# PSD_PMIC.net
KiCad netlist of a schematic drawn in Altium Designer
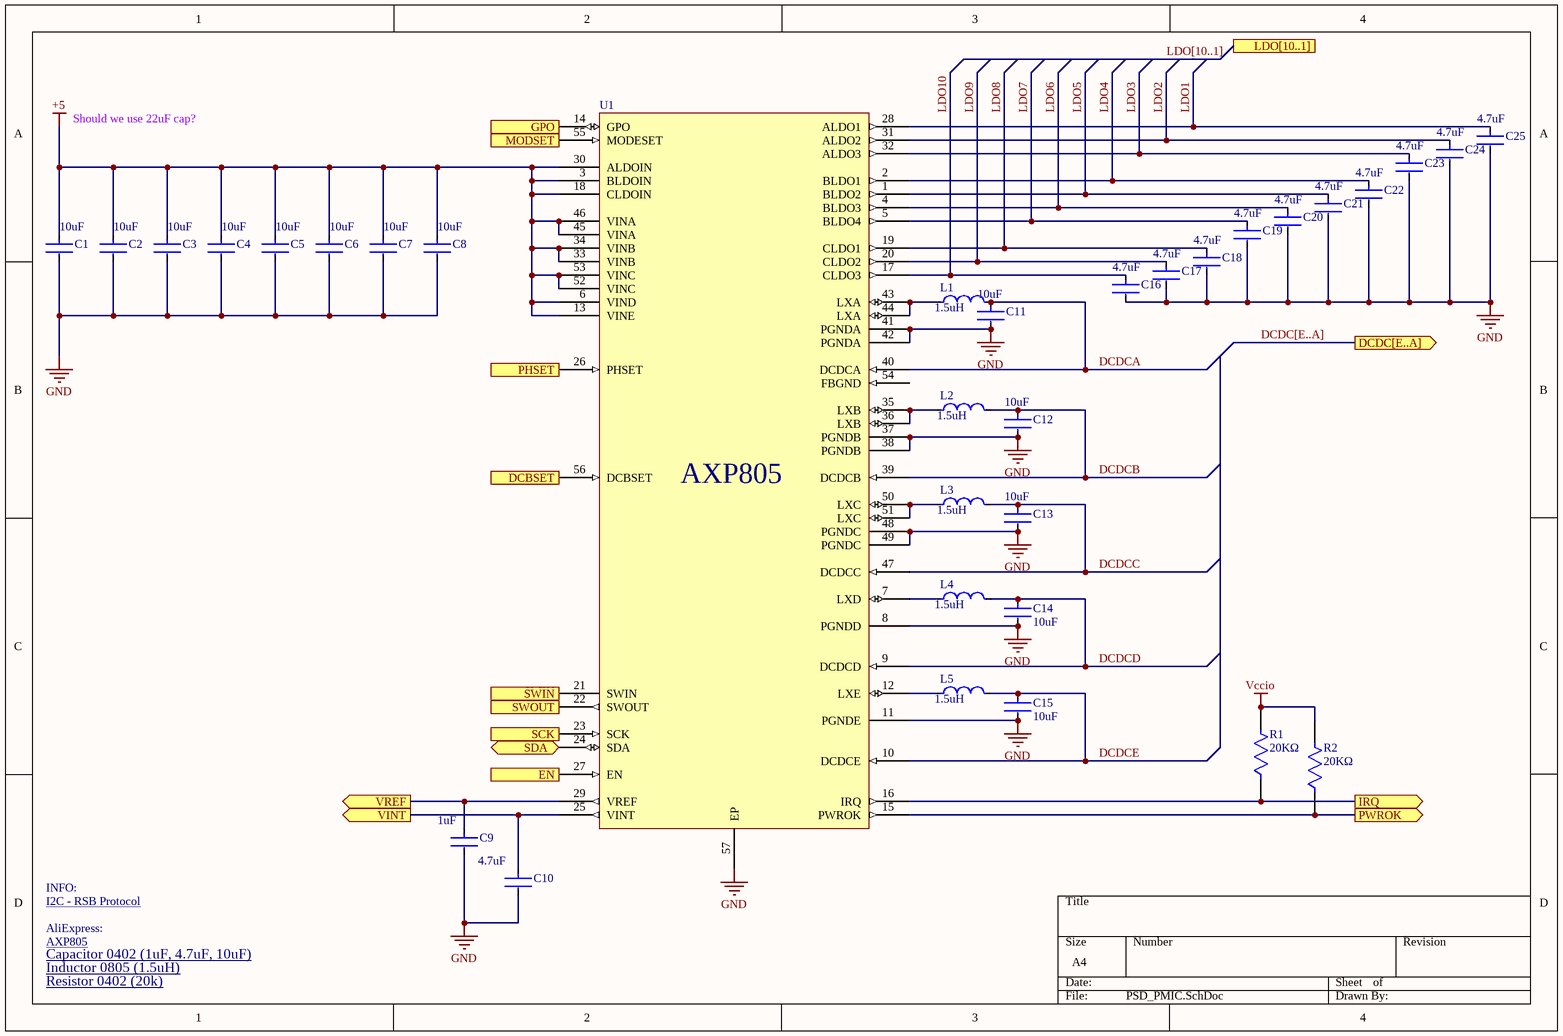
[diagram p0: PSD_PMIC.SchDoc]

(export (version "E")
  (design (tool "Eeschema 10.0.6"))
  (components
    (comp (ref "C1")
      (value "CL05A106MP5NUNC")
      (footprint "FP-CL05A106MP5NUNC-MFG")
      (description "CAP CER 10UF 10V X5R 0402")
      (fields
        (field (name "OCTOPART") "https://octopart.com/cl05a106mp5nunc-samsung-22457395")
        (field (name "TOLERANCE") "20%")
        (field (name "CAPACITANCE") "10uF")
      )
      (libsource (lib "Altium Content Vault") (part "b4654b650e69147ec39a6b967a45e02"))
    )
    (comp (ref "C2")
      (value "CL05A106MP5NUNC")
      (footprint "FP-CL05A106MP5NUNC-MFG")
      (description "CAP CER 10UF 10V X5R 0402")
      (fields
        (field (name "OCTOPART") "https://octopart.com/cl05a106mp5nunc-samsung-22457395")
        (field (name "TOLERANCE") "20%")
        (field (name "CAPACITANCE") "10uF")
      )
      (libsource (lib "Altium Content Vault") (part "b4654b650e69147ec39a6b967a45e02"))
    )
    (comp (ref "C3")
      (value "CL05A106MP5NUNC")
      (footprint "FP-CL05A106MP5NUNC-MFG")
      (description "CAP CER 10UF 10V X5R 0402")
      (fields
        (field (name "OCTOPART") "https://octopart.com/cl05a106mp5nunc-samsung-22457395")
        (field (name "TOLERANCE") "20%")
        (field (name "CAPACITANCE") "10uF")
      )
      (libsource (lib "Altium Content Vault") (part "b4654b650e69147ec39a6b967a45e02"))
    )
    (comp (ref "C4")
      (value "CL05A106MP5NUNC")
      (footprint "FP-CL05A106MP5NUNC-MFG")
      (description "CAP CER 10UF 10V X5R 0402")
      (fields
        (field (name "OCTOPART") "https://octopart.com/cl05a106mp5nunc-samsung-22457395")
        (field (name "TOLERANCE") "20%")
        (field (name "CAPACITANCE") "10uF")
      )
      (libsource (lib "Altium Content Vault") (part "b4654b650e69147ec39a6b967a45e02"))
    )
    (comp (ref "C5")
      (value "CL05A106MP5NUNC")
      (footprint "FP-CL05A106MP5NUNC-MFG")
      (description "CAP CER 10UF 10V X5R 0402")
      (fields
        (field (name "OCTOPART") "https://octopart.com/cl05a106mp5nunc-samsung-22457395")
        (field (name "TOLERANCE") "20%")
        (field (name "CAPACITANCE") "10uF")
      )
      (libsource (lib "Altium Content Vault") (part "b4654b650e69147ec39a6b967a45e02"))
    )
    (comp (ref "C6")
      (value "CL05A106MP5NUNC")
      (footprint "FP-CL05A106MP5NUNC-MFG")
      (description "CAP CER 10UF 10V X5R 0402")
      (fields
        (field (name "OCTOPART") "https://octopart.com/cl05a106mp5nunc-samsung-22457395")
        (field (name "TOLERANCE") "20%")
        (field (name "CAPACITANCE") "10uF")
      )
      (libsource (lib "Altium Content Vault") (part "b4654b650e69147ec39a6b967a45e02"))
    )
    (comp (ref "C7")
      (value "CL05A106MP5NUNC")
      (footprint "FP-CL05A106MP5NUNC-MFG")
      (description "CAP CER 10UF 10V X5R 0402")
      (fields
        (field (name "OCTOPART") "https://octopart.com/cl05a106mp5nunc-samsung-22457395")
        (field (name "TOLERANCE") "20%")
        (field (name "CAPACITANCE") "10uF")
      )
      (libsource (lib "Altium Content Vault") (part "b4654b650e69147ec39a6b967a45e02"))
    )
    (comp (ref "C8")
      (value "CL05A106MP5NUNC")
      (footprint "FP-CL05A106MP5NUNC-MFG")
      (description "CAP CER 10UF 10V X5R 0402")
      (fields
        (field (name "OCTOPART") "https://octopart.com/cl05a106mp5nunc-samsung-22457395")
        (field (name "TOLERANCE") "20%")
        (field (name "CAPACITANCE") "10uF")
      )
      (libsource (lib "Altium Content Vault") (part "b4654b650e69147ec39a6b967a45e02"))
    )
    (comp (ref "C9")
      (value "CL05B105KQ5NQNC")
      (footprint "FP-CL95-IPC_C")
      (description "Cap Ceramic 1uF 6.3V X7R ±10% SMD 0402 +125°C Paper T/R")
      (fields (field (name "CAPACITANCE") "1uF") (field (name "TOLERANCE") "10%"))
      (libsource (lib "Altium Content Vault") (part "b4654b650e69147ec39a6b967a45e02"))
    )
    (comp (ref "C10")
      (value "CL05A475KP5NRNC")
      (footprint "FP-CL828-IPC_C")
      (description "Cap Ceramic 4.7uF 10V X5R ±10% SMD 0402 +85°C Paper T/R")
      (fields (field (name "CAPACITANCE") "4.7uF") (field (name "TOLERANCE") "10%"))
      (libsource (lib "Altium Content Vault") (part "b4654b650e69147ec39a6b967a45e02"))
    )
    (comp (ref "C11")
      (value "CL05A106MP5NUNC")
      (footprint "FP-CL05A106MP5NUNC-MFG")
      (description "CAP CER 10UF 10V X5R 0402")
      (fields
        (field (name "OCTOPART") "https://octopart.com/cl05a106mp5nunc-samsung-22457395")
        (field (name "TOLERANCE") "20%")
        (field (name "CAPACITANCE") "10uF")
      )
      (libsource (lib "Altium Content Vault") (part "b4654b650e69147ec39a6b967a45e02"))
    )
    (comp (ref "C12")
      (value "CL05A106MP5NUNC")
      (footprint "FP-CL05A106MP5NUNC-MFG")
      (description "CAP CER 10UF 10V X5R 0402")
      (fields
        (field (name "OCTOPART") "https://octopart.com/cl05a106mp5nunc-samsung-22457395")
        (field (name "TOLERANCE") "20%")
        (field (name "CAPACITANCE") "10uF")
      )
      (libsource (lib "Altium Content Vault") (part "b4654b650e69147ec39a6b967a45e02"))
    )
    (comp (ref "C13")
      (value "CL05A106MP5NUNC")
      (footprint "FP-CL05A106MP5NUNC-MFG")
      (description "CAP CER 10UF 10V X5R 0402")
      (fields
        (field (name "OCTOPART") "https://octopart.com/cl05a106mp5nunc-samsung-22457395")
        (field (name "TOLERANCE") "20%")
        (field (name "CAPACITANCE") "10uF")
      )
      (libsource (lib "Altium Content Vault") (part "b4654b650e69147ec39a6b967a45e02"))
    )
    (comp (ref "C14")
      (value "CL05A106MP5NUNC")
      (footprint "FP-CL05A106MP5NUNC-MFG")
      (description "CAP CER 10UF 10V X5R 0402")
      (fields
        (field (name "OCTOPART") "https://octopart.com/cl05a106mp5nunc-samsung-22457395")
        (field (name "TOLERANCE") "20%")
        (field (name "CAPACITANCE") "10uF")
      )
      (libsource (lib "Altium Content Vault") (part "b4654b650e69147ec39a6b967a45e02"))
    )
    (comp (ref "C15")
      (value "CL05A106MP5NUNC")
      (footprint "FP-CL05A106MP5NUNC-MFG")
      (description "CAP CER 10UF 10V X5R 0402")
      (fields
        (field (name "OCTOPART") "https://octopart.com/cl05a106mp5nunc-samsung-22457395")
        (field (name "TOLERANCE") "20%")
        (field (name "CAPACITANCE") "10uF")
      )
      (libsource (lib "Altium Content Vault") (part "b4654b650e69147ec39a6b967a45e02"))
    )
    (comp (ref "C16")
      (value "CL05A475KP5NRNC")
      (footprint "FP-CL828-IPC_C")
      (description "Cap Ceramic 4.7uF 10V X5R ±10% SMD 0402 +85°C Paper T/R")
      (fields (field (name "CAPACITANCE") "4.7uF") (field (name "TOLERANCE") "10%"))
      (libsource (lib "Altium Content Vault") (part "b4654b650e69147ec39a6b967a45e02"))
    )
    (comp (ref "C17")
      (value "CL05A475KP5NRNC")
      (footprint "FP-CL828-IPC_C")
      (description "Cap Ceramic 4.7uF 10V X5R ±10% SMD 0402 +85°C Paper T/R")
      (fields (field (name "CAPACITANCE") "4.7uF") (field (name "TOLERANCE") "10%"))
      (libsource (lib "Altium Content Vault") (part "b4654b650e69147ec39a6b967a45e02"))
    )
    (comp (ref "C18")
      (value "CL05A475KP5NRNC")
      (footprint "FP-CL828-IPC_C")
      (description "Cap Ceramic 4.7uF 10V X5R ±10% SMD 0402 +85°C Paper T/R")
      (fields (field (name "CAPACITANCE") "4.7uF") (field (name "TOLERANCE") "10%"))
      (libsource (lib "Altium Content Vault") (part "b4654b650e69147ec39a6b967a45e02"))
    )
    (comp (ref "C19")
      (value "CL05A475KP5NRNC")
      (footprint "FP-CL828-IPC_C")
      (description "Cap Ceramic 4.7uF 10V X5R ±10% SMD 0402 +85°C Paper T/R")
      (fields (field (name "CAPACITANCE") "4.7uF") (field (name "TOLERANCE") "10%"))
      (libsource (lib "Altium Content Vault") (part "b4654b650e69147ec39a6b967a45e02"))
    )
    (comp (ref "C20")
      (value "CL05A475KP5NRNC")
      (footprint "FP-CL828-IPC_C")
      (description "Cap Ceramic 4.7uF 10V X5R ±10% SMD 0402 +85°C Paper T/R")
      (fields (field (name "CAPACITANCE") "4.7uF") (field (name "TOLERANCE") "10%"))
      (libsource (lib "Altium Content Vault") (part "b4654b650e69147ec39a6b967a45e02"))
    )
    (comp (ref "C21")
      (value "CL05A475KP5NRNC")
      (footprint "FP-CL828-IPC_C")
      (description "Cap Ceramic 4.7uF 10V X5R ±10% SMD 0402 +85°C Paper T/R")
      (fields (field (name "CAPACITANCE") "4.7uF") (field (name "TOLERANCE") "10%"))
      (libsource (lib "Altium Content Vault") (part "b4654b650e69147ec39a6b967a45e02"))
    )
    (comp (ref "C22")
      (value "CL05A475KP5NRNC")
      (footprint "FP-CL828-IPC_C")
      (description "Cap Ceramic 4.7uF 10V X5R ±10% SMD 0402 +85°C Paper T/R")
      (fields (field (name "CAPACITANCE") "4.7uF") (field (name "TOLERANCE") "10%"))
      (libsource (lib "Altium Content Vault") (part "b4654b650e69147ec39a6b967a45e02"))
    )
    (comp (ref "C23")
      (value "CL05A475KP5NRNC")
      (footprint "FP-CL828-IPC_C")
      (description "Cap Ceramic 4.7uF 10V X5R ±10% SMD 0402 +85°C Paper T/R")
      (fields (field (name "CAPACITANCE") "4.7uF") (field (name "TOLERANCE") "10%"))
      (libsource (lib "Altium Content Vault") (part "b4654b650e69147ec39a6b967a45e02"))
    )
    (comp (ref "C24")
      (value "CL05A475KP5NRNC")
      (footprint "FP-CL828-IPC_C")
      (description "Cap Ceramic 4.7uF 10V X5R ±10% SMD 0402 +85°C Paper T/R")
      (fields (field (name "CAPACITANCE") "4.7uF") (field (name "TOLERANCE") "10%"))
      (libsource (lib "Altium Content Vault") (part "b4654b650e69147ec39a6b967a45e02"))
    )
    (comp (ref "C25")
      (value "CL05A475KP5NRNC")
      (footprint "FP-CL828-IPC_C")
      (description "Cap Ceramic 4.7uF 10V X5R ±10% SMD 0402 +85°C Paper T/R")
      (fields (field (name "CAPACITANCE") "4.7uF") (field (name "TOLERANCE") "10%"))
      (libsource (lib "Altium Content Vault") (part "b4654b650e69147ec39a6b967a45e02"))
    )
    (comp (ref "L1")
      (value "LQM21NN1R5K10D")
      (footprint "FP-LQM21DN_00-MFG")
      (description "Multilayer Type Inductor for General Circuits, 0805 (2012), 1.5μH, 10%, 0.5Ω, 50mA")
      (fields (field (name "TOLERANCE") "10%") (field (name "INDUCTANCE") "1.5uH"))
      (libsource (lib "Altium Content Vault") (part "725321dda6339637d4d059423bc1c3c"))
    )
    (comp (ref "L2")
      (value "LQM21NN1R5K10D")
      (footprint "FP-LQM21DN_00-MFG")
      (description "Multilayer Type Inductor for General Circuits, 0805 (2012), 1.5μH, 10%, 0.5Ω, 50mA")
      (fields (field (name "TOLERANCE") "10%") (field (name "INDUCTANCE") "1.5uH"))
      (libsource (lib "Altium Content Vault") (part "725321dda6339637d4d059423bc1c3c"))
    )
    (comp (ref "L3")
      (value "LQM21NN1R5K10D")
      (footprint "FP-LQM21DN_00-MFG")
      (description "Multilayer Type Inductor for General Circuits, 0805 (2012), 1.5μH, 10%, 0.5Ω, 50mA")
      (fields (field (name "TOLERANCE") "10%") (field (name "INDUCTANCE") "1.5uH"))
      (libsource (lib "Altium Content Vault") (part "725321dda6339637d4d059423bc1c3c"))
    )
    (comp (ref "L4")
      (value "LQM21NN1R5K10D")
      (footprint "FP-LQM21DN_00-MFG")
      (description "Multilayer Type Inductor for General Circuits, 0805 (2012), 1.5μH, 10%, 0.5Ω, 50mA")
      (fields (field (name "TOLERANCE") "10%") (field (name "INDUCTANCE") "1.5uH"))
      (libsource (lib "Altium Content Vault") (part "725321dda6339637d4d059423bc1c3c"))
    )
    (comp (ref "L5")
      (value "LQM21NN1R5K10D")
      (footprint "FP-LQM21DN_00-MFG")
      (description "Multilayer Type Inductor for General Circuits, 0805 (2012), 1.5μH, 10%, 0.5Ω, 50mA")
      (fields (field (name "TOLERANCE") "10%") (field (name "INDUCTANCE") "1.5uH"))
      (libsource (lib "Altium Content Vault") (part "725321dda6339637d4d059423bc1c3c"))
    )
    (comp (ref "R1")
      (value "20KΩ")
      (footprint "FP-RT0402-MFG")
      (description "RES SMD 20K OHM 0.1% 1/16W 0402")
      (fields
        (field (name "MANUFACTURER PART NUMBER") "RT0402BRD0720KL")
        (field (name "OCTOPART") "https://octopart.com/rt0402brd0720kl-yageo-1422805")
      )
      (libsource (lib "Altium Content Vault") (part "1029c3af85768c4190bb7ad29bc67b5"))
    )
    (comp (ref "R2")
      (value "20KΩ")
      (footprint "FP-RT0402-MFG")
      (description "RES SMD 20K OHM 0.1% 1/16W 0402")
      (fields
        (field (name "MANUFACTURER PART NUMBER") "RT0402BRD0720KL")
        (field (name "OCTOPART") "https://octopart.com/rt0402brd0720kl-yageo-1422805")
      )
      (libsource (lib "Altium Content Vault") (part "1029c3af85768c4190bb7ad29bc67b5"))
    )
    (comp (ref "U1")
      (value "UQFN127P600-8N")
      (footprint "UQFN127P600-8N")
      (libsource (lib "CUSTOM") (part "UQFN127P600-8N"))
    )
  )
  (nets
    (net (code "2") (name "+5") (class "Default")
      (node (ref "C1") (pin "1") (pinfunction "1_1") (pintype "passive"))
      (node (ref "C2") (pin "1") (pinfunction "1_1") (pintype "passive"))
      (node (ref "C3") (pin "1") (pinfunction "1_1") (pintype "passive"))
      (node (ref "C4") (pin "1") (pinfunction "1_1") (pintype "passive"))
      (node (ref "C5") (pin "1") (pinfunction "1_1") (pintype "passive"))
      (node (ref "C6") (pin "1") (pinfunction "1_1") (pintype "passive"))
      (node (ref "C7") (pin "1") (pinfunction "1_1") (pintype "passive"))
      (node (ref "C8") (pin "1") (pinfunction "1_1") (pintype "passive"))
      (node (ref "U1") (pin "13") (pinfunction "VINE_13") (pintype "power_in"))
      (node (ref "U1") (pin "18") (pinfunction "CLDOIN_18") (pintype "power_in"))
      (node (ref "U1") (pin "3") (pinfunction "BLDOIN_3") (pintype "power_in"))
      (node (ref "U1") (pin "30") (pinfunction "ALDOIN_30") (pintype "power_in"))
      (node (ref "U1") (pin "33") (pinfunction "VINB_33") (pintype "power_in"))
      (node (ref "U1") (pin "34") (pinfunction "VINB_34") (pintype "power_in"))
      (node (ref "U1") (pin "45") (pinfunction "VINA_45") (pintype "power_in"))
      (node (ref "U1") (pin "46") (pinfunction "VINA_46") (pintype "power_in"))
      (node (ref "U1") (pin "52") (pinfunction "VINC_52") (pintype "power_in"))
      (node (ref "U1") (pin "53") (pinfunction "VINC_53") (pintype "power_in"))
      (node (ref "U1") (pin "6") (pinfunction "VIND_6") (pintype "power_in"))
    )
    (net (code "3") (name "/DCBSET") (class "Default")
      (node (ref "U1") (pin "56") (pinfunction "DCBSET_56") (pintype "input"))
    )
    (net (code "4") (name "/DCDCA") (class "Default")
      (node (ref "C11") (pin "1") (pinfunction "1_1") (pintype "passive"))
      (node (ref "L1") (pin "2") (pinfunction "2_2") (pintype "passive"))
      (node (ref "U1") (pin "40") (pinfunction "DCDCA_40") (pintype "input"))
    )
    (net (code "5") (name "/DCDCB") (class "Default")
      (node (ref "C12") (pin "1") (pinfunction "1_1") (pintype "passive"))
      (node (ref "L2") (pin "2") (pinfunction "2_2") (pintype "passive"))
      (node (ref "U1") (pin "39") (pinfunction "DCDCB_39") (pintype "input"))
    )
    (net (code "6") (name "/DCDCC") (class "Default")
      (node (ref "C13") (pin "1") (pinfunction "1_1") (pintype "passive"))
      (node (ref "L3") (pin "2") (pinfunction "2_2") (pintype "passive"))
      (node (ref "U1") (pin "47") (pinfunction "DCDCC_47") (pintype "input"))
    )
    (net (code "7") (name "/DCDCD") (class "Default")
      (node (ref "C14") (pin "1") (pinfunction "1_1") (pintype "passive"))
      (node (ref "L4") (pin "2") (pinfunction "2_2") (pintype "passive"))
      (node (ref "U1") (pin "9") (pinfunction "DCDCD_9") (pintype "input"))
    )
    (net (code "8") (name "/DCDCE") (class "Default")
      (node (ref "C15") (pin "1") (pinfunction "1_1") (pintype "passive"))
      (node (ref "L5") (pin "2") (pinfunction "2_2") (pintype "passive"))
      (node (ref "U1") (pin "10") (pinfunction "DCDCE_10") (pintype "input"))
    )
    (net (code "9") (name "/EN") (class "Default")
      (node (ref "U1") (pin "27") (pinfunction "EN_27") (pintype "input"))
    )
    (net (code "10") (name "/GPO") (class "Default")
      (node (ref "U1") (pin "14") (pinfunction "GPO_14") (pintype "bidirectional"))
    )
    (net (code "11") (name "/IRQ") (class "Default")
      (node (ref "R1") (pin "1") (pinfunction "1_1") (pintype "passive"))
      (node (ref "U1") (pin "16") (pinfunction "IRQ_16") (pintype "output"))
    )
    (net (code "12") (name "/LDO1") (class "Default")
      (node (ref "C25") (pin "1") (pinfunction "1_1") (pintype "passive"))
      (node (ref "U1") (pin "28") (pinfunction "ALDO1_28") (pintype "output"))
    )
    (net (code "13") (name "/LDO2") (class "Default")
      (node (ref "C24") (pin "1") (pinfunction "1_1") (pintype "passive"))
      (node (ref "U1") (pin "31") (pinfunction "ALDO2_31") (pintype "output"))
    )
    (net (code "14") (name "/LDO3") (class "Default")
      (node (ref "C23") (pin "1") (pinfunction "1_1") (pintype "passive"))
      (node (ref "U1") (pin "32") (pinfunction "ALDO3_32") (pintype "output"))
    )
    (net (code "15") (name "/LDO4") (class "Default")
      (node (ref "C22") (pin "1") (pinfunction "1_1") (pintype "passive"))
      (node (ref "U1") (pin "2") (pinfunction "BLDO1_2") (pintype "output"))
    )
    (net (code "16") (name "/LDO5") (class "Default")
      (node (ref "C21") (pin "1") (pinfunction "1_1") (pintype "passive"))
      (node (ref "U1") (pin "1") (pinfunction "BLDO2_1") (pintype "output"))
    )
    (net (code "17") (name "/LDO6") (class "Default")
      (node (ref "C20") (pin "1") (pinfunction "1_1") (pintype "passive"))
      (node (ref "U1") (pin "4") (pinfunction "BLDO3_4") (pintype "output"))
    )
    (net (code "18") (name "/LDO7") (class "Default")
      (node (ref "C19") (pin "1") (pinfunction "1_1") (pintype "passive"))
      (node (ref "U1") (pin "5") (pinfunction "BLDO4_5") (pintype "output"))
    )
    (net (code "19") (name "/LDO8") (class "Default")
      (node (ref "C18") (pin "1") (pinfunction "1_1") (pintype "passive"))
      (node (ref "U1") (pin "19") (pinfunction "CLDO1_19") (pintype "output"))
    )
    (net (code "20") (name "/LDO9") (class "Default")
      (node (ref "C17") (pin "1") (pinfunction "1_1") (pintype "passive"))
      (node (ref "U1") (pin "20") (pinfunction "CLDO2_20") (pintype "output"))
    )
    (net (code "21") (name "/LDO10") (class "Default")
      (node (ref "C16") (pin "1") (pinfunction "1_1") (pintype "passive"))
      (node (ref "U1") (pin "17") (pinfunction "CLDO3_17") (pintype "output"))
    )
    (net (code "23") (name "/MODSET") (class "Default")
      (node (ref "U1") (pin "55") (pinfunction "MODESET_55") (pintype "input"))
    )
    (net (code "24") (name "/PHSET") (class "Default")
      (node (ref "U1") (pin "26") (pinfunction "PHSET_26") (pintype "input"))
    )
    (net (code "25") (name "/PWROK") (class "Default")
      (node (ref "R2") (pin "1") (pinfunction "1_1") (pintype "passive"))
      (node (ref "U1") (pin "15") (pinfunction "PWROK_15") (pintype "output"))
    )
    (net (code "26") (name "/SCK") (class "Default")
      (node (ref "U1") (pin "23") (pinfunction "SCK_23") (pintype "input"))
    )
    (net (code "27") (name "/SDA") (class "Default")
      (node (ref "U1") (pin "24") (pinfunction "SDA_24") (pintype "bidirectional"))
    )
    (net (code "28") (name "/SWIN") (class "Default")
      (node (ref "U1") (pin "21") (pinfunction "SWIN_21") (pintype "power_in"))
    )
    (net (code "29") (name "/SWOUT") (class "Default")
      (node (ref "U1") (pin "22") (pinfunction "SWOUT_22") (pintype "output"))
    )
    (net (code "30") (name "/VINT") (class "Default")
      (node (ref "C10") (pin "1") (pinfunction "1_1") (pintype "passive"))
      (node (ref "U1") (pin "25") (pinfunction "VINT_25") (pintype "output"))
    )
    (net (code "31") (name "/VREF") (class "Default")
      (node (ref "C9") (pin "1") (pinfunction "1_1") (pintype "passive"))
      (node (ref "U1") (pin "29") (pinfunction "VREF_29") (pintype "output"))
    )
    (net (code "33") (name "GND") (class "Default")
      (node (ref "C1") (pin "2") (pinfunction "2_2") (pintype "passive"))
      (node (ref "C10") (pin "2") (pinfunction "2_2") (pintype "passive"))
      (node (ref "C11") (pin "2") (pinfunction "2_2") (pintype "passive"))
      (node (ref "C12") (pin "2") (pinfunction "2_2") (pintype "passive"))
      (node (ref "C13") (pin "2") (pinfunction "2_2") (pintype "passive"))
      (node (ref "C14") (pin "2") (pinfunction "2_2") (pintype "passive"))
      (node (ref "C15") (pin "2") (pinfunction "2_2") (pintype "passive"))
      (node (ref "C16") (pin "2") (pinfunction "2_2") (pintype "passive"))
      (node (ref "C17") (pin "2") (pinfunction "2_2") (pintype "passive"))
      (node (ref "C18") (pin "2") (pinfunction "2_2") (pintype "passive"))
      (node (ref "C19") (pin "2") (pinfunction "2_2") (pintype "passive"))
      (node (ref "C2") (pin "2") (pinfunction "2_2") (pintype "passive"))
      (node (ref "C20") (pin "2") (pinfunction "2_2") (pintype "passive"))
      (node (ref "C21") (pin "2") (pinfunction "2_2") (pintype "passive"))
      (node (ref "C22") (pin "2") (pinfunction "2_2") (pintype "passive"))
      (node (ref "C23") (pin "2") (pinfunction "2_2") (pintype "passive"))
      (node (ref "C24") (pin "2") (pinfunction "2_2") (pintype "passive"))
      (node (ref "C25") (pin "2") (pinfunction "2_2") (pintype "passive"))
      (node (ref "C3") (pin "2") (pinfunction "2_2") (pintype "passive"))
      (node (ref "C4") (pin "2") (pinfunction "2_2") (pintype "passive"))
      (node (ref "C5") (pin "2") (pinfunction "2_2") (pintype "passive"))
      (node (ref "C6") (pin "2") (pinfunction "2_2") (pintype "passive"))
      (node (ref "C7") (pin "2") (pinfunction "2_2") (pintype "passive"))
      (node (ref "C8") (pin "2") (pinfunction "2_2") (pintype "passive"))
      (node (ref "C9") (pin "2") (pinfunction "2_2") (pintype "passive"))
      (node (ref "U1") (pin "11") (pinfunction "PGNDE_11") (pintype "passive"))
      (node (ref "U1") (pin "37") (pinfunction "PGNDB_37") (pintype "passive"))
      (node (ref "U1") (pin "38") (pinfunction "PGNDB_38") (pintype "passive"))
      (node (ref "U1") (pin "41") (pinfunction "PGNDA_41") (pintype "passive"))
      (node (ref "U1") (pin "42") (pinfunction "PGNDA_42") (pintype "passive"))
      (node (ref "U1") (pin "48") (pinfunction "PGNDC_48") (pintype "passive"))
      (node (ref "U1") (pin "49") (pinfunction "PGNDC_49") (pintype "passive"))
      (node (ref "U1") (pin "57") (pinfunction "EP_57") (pintype "passive"))
      (node (ref "U1") (pin "8") (pinfunction "PGNDD_8") (pintype "passive"))
    )
    (net (code "34") (name "Net-(L1-Pad1)") (class "Default")
      (node (ref "L1") (pin "1") (pinfunction "1_1") (pintype "passive"))
      (node (ref "U1") (pin "43") (pinfunction "LXA_43") (pintype "bidirectional"))
      (node (ref "U1") (pin "44") (pinfunction "LXA_44") (pintype "bidirectional"))
    )
    (net (code "35") (name "Net-(L2-Pad1)") (class "Default")
      (node (ref "L2") (pin "1") (pinfunction "1_1") (pintype "passive"))
      (node (ref "U1") (pin "35") (pinfunction "LXB_35") (pintype "bidirectional"))
      (node (ref "U1") (pin "36") (pinfunction "LXB_36") (pintype "bidirectional"))
    )
    (net (code "36") (name "Net-(L3-Pad1)") (class "Default")
      (node (ref "L3") (pin "1") (pinfunction "1_1") (pintype "passive"))
      (node (ref "U1") (pin "50") (pinfunction "LXC_50") (pintype "bidirectional"))
      (node (ref "U1") (pin "51") (pinfunction "LXC_51") (pintype "bidirectional"))
    )
    (net (code "37") (name "Net-(U1-LXD)") (class "Default")
      (node (ref "L4") (pin "1") (pinfunction "1_1") (pintype "passive"))
      (node (ref "U1") (pin "7") (pinfunction "LXD_7") (pintype "bidirectional"))
    )
    (net (code "38") (name "Net-(U1-LXE)") (class "Default")
      (node (ref "L5") (pin "1") (pinfunction "1_1") (pintype "passive"))
      (node (ref "U1") (pin "12") (pinfunction "LXE_12") (pintype "bidirectional"))
    )
    (net (code "39") (name "Vccio") (class "Default")
      (node (ref "R1") (pin "2") (pinfunction "2_2") (pintype "passive"))
      (node (ref "R2") (pin "2") (pinfunction "2_2") (pintype "passive"))
    )
    (net (code "40") (name "unconnected-(U1-FBGND-Pad54)") (class "Default")
      (node (ref "U1") (pin "54") (pinfunction "FBGND_54") (pintype "input"))
    )
  )
)
